# picrocope_hub_v3r1.net
KiCad netlist of a schematic drawn in EAGLE
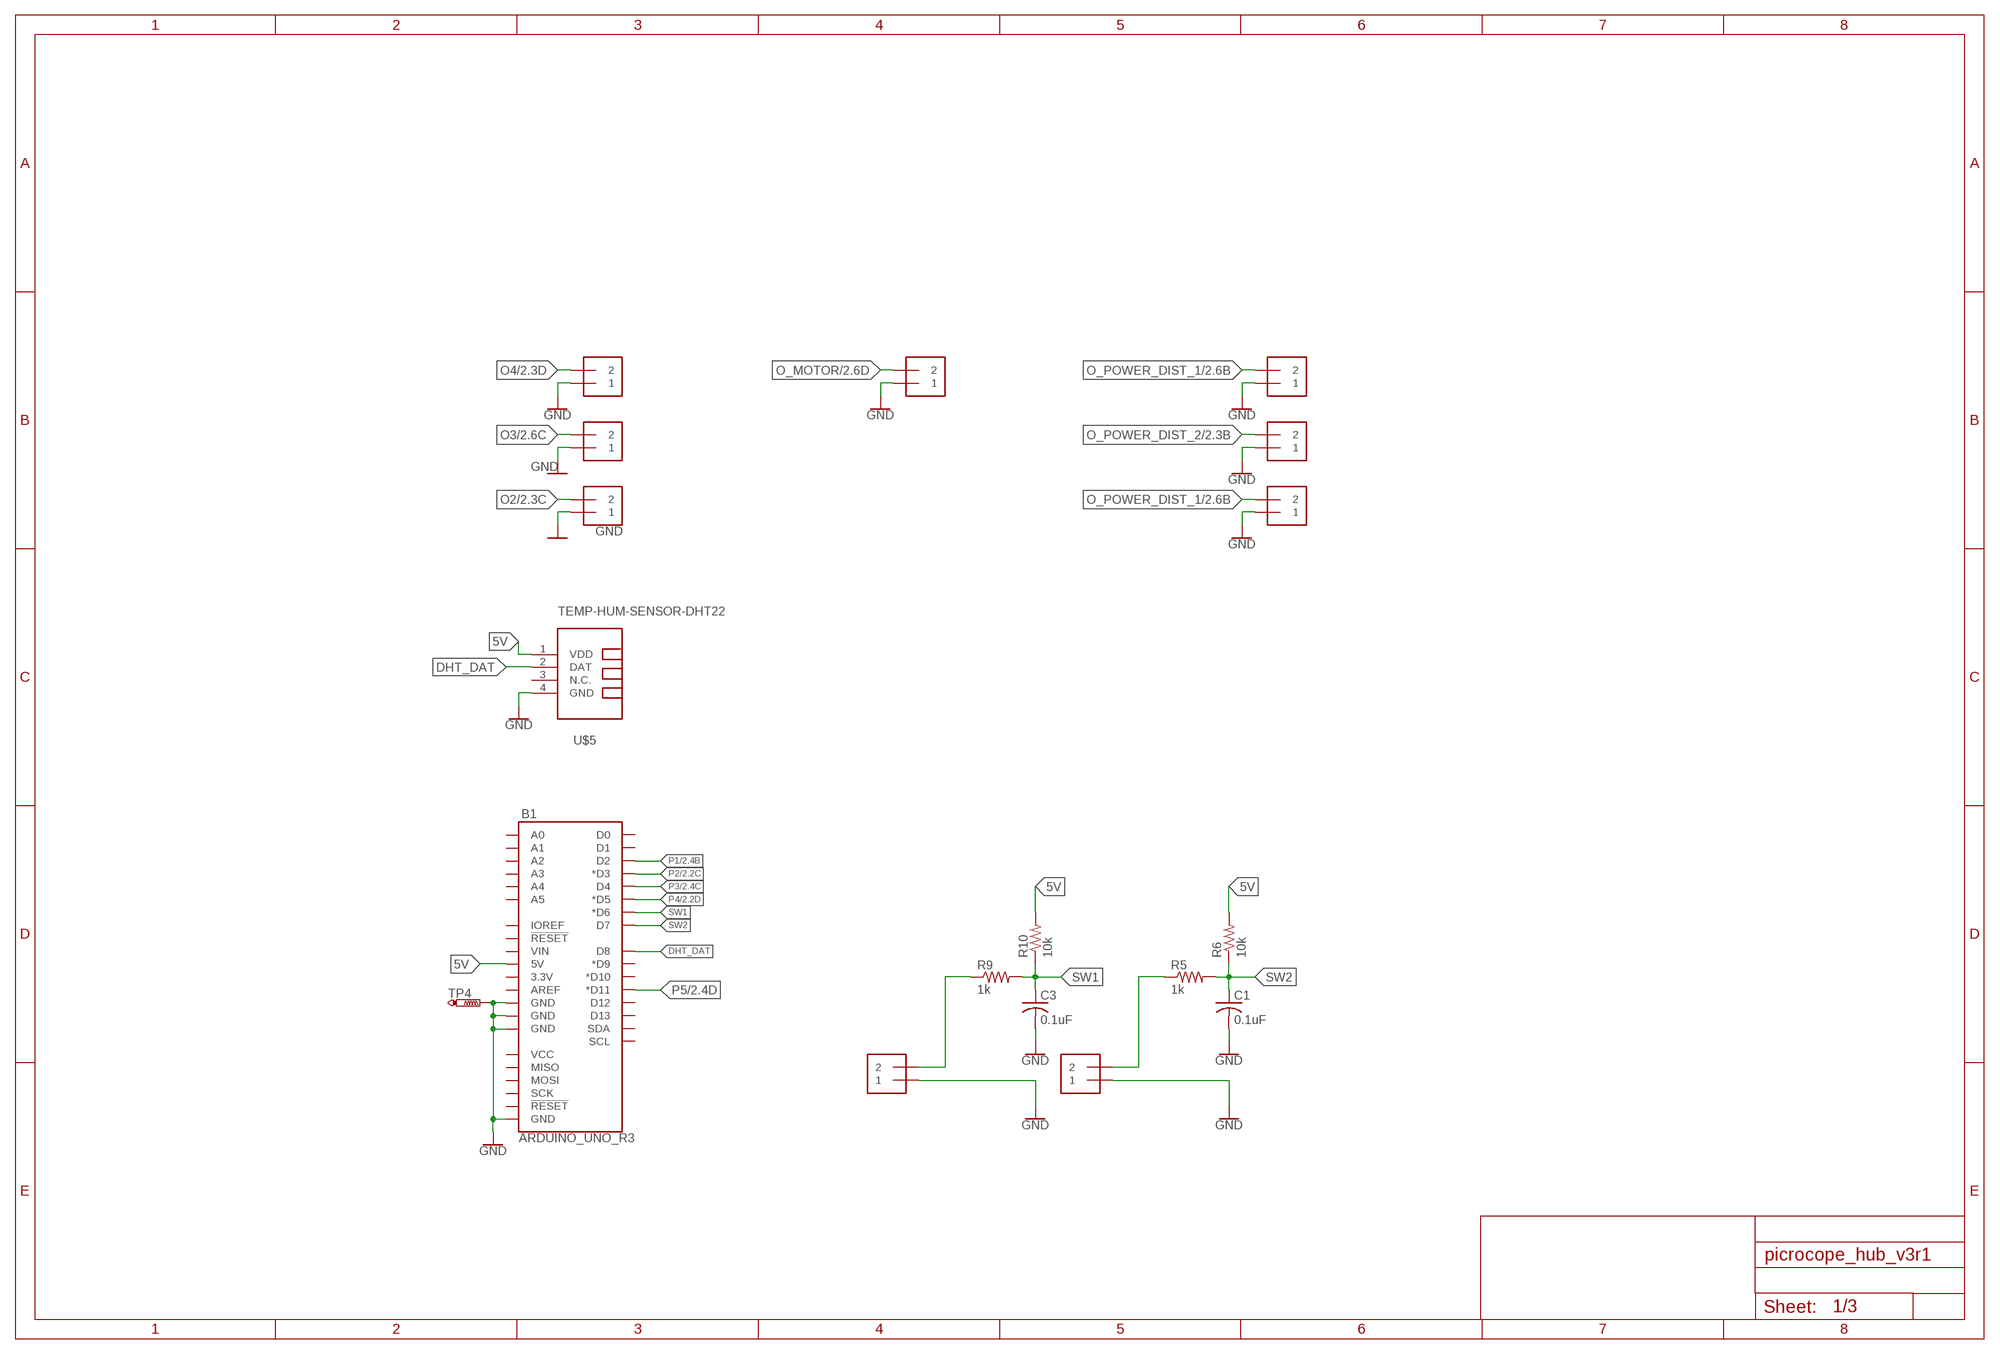
[diagram p0: schematic, sheet 1]
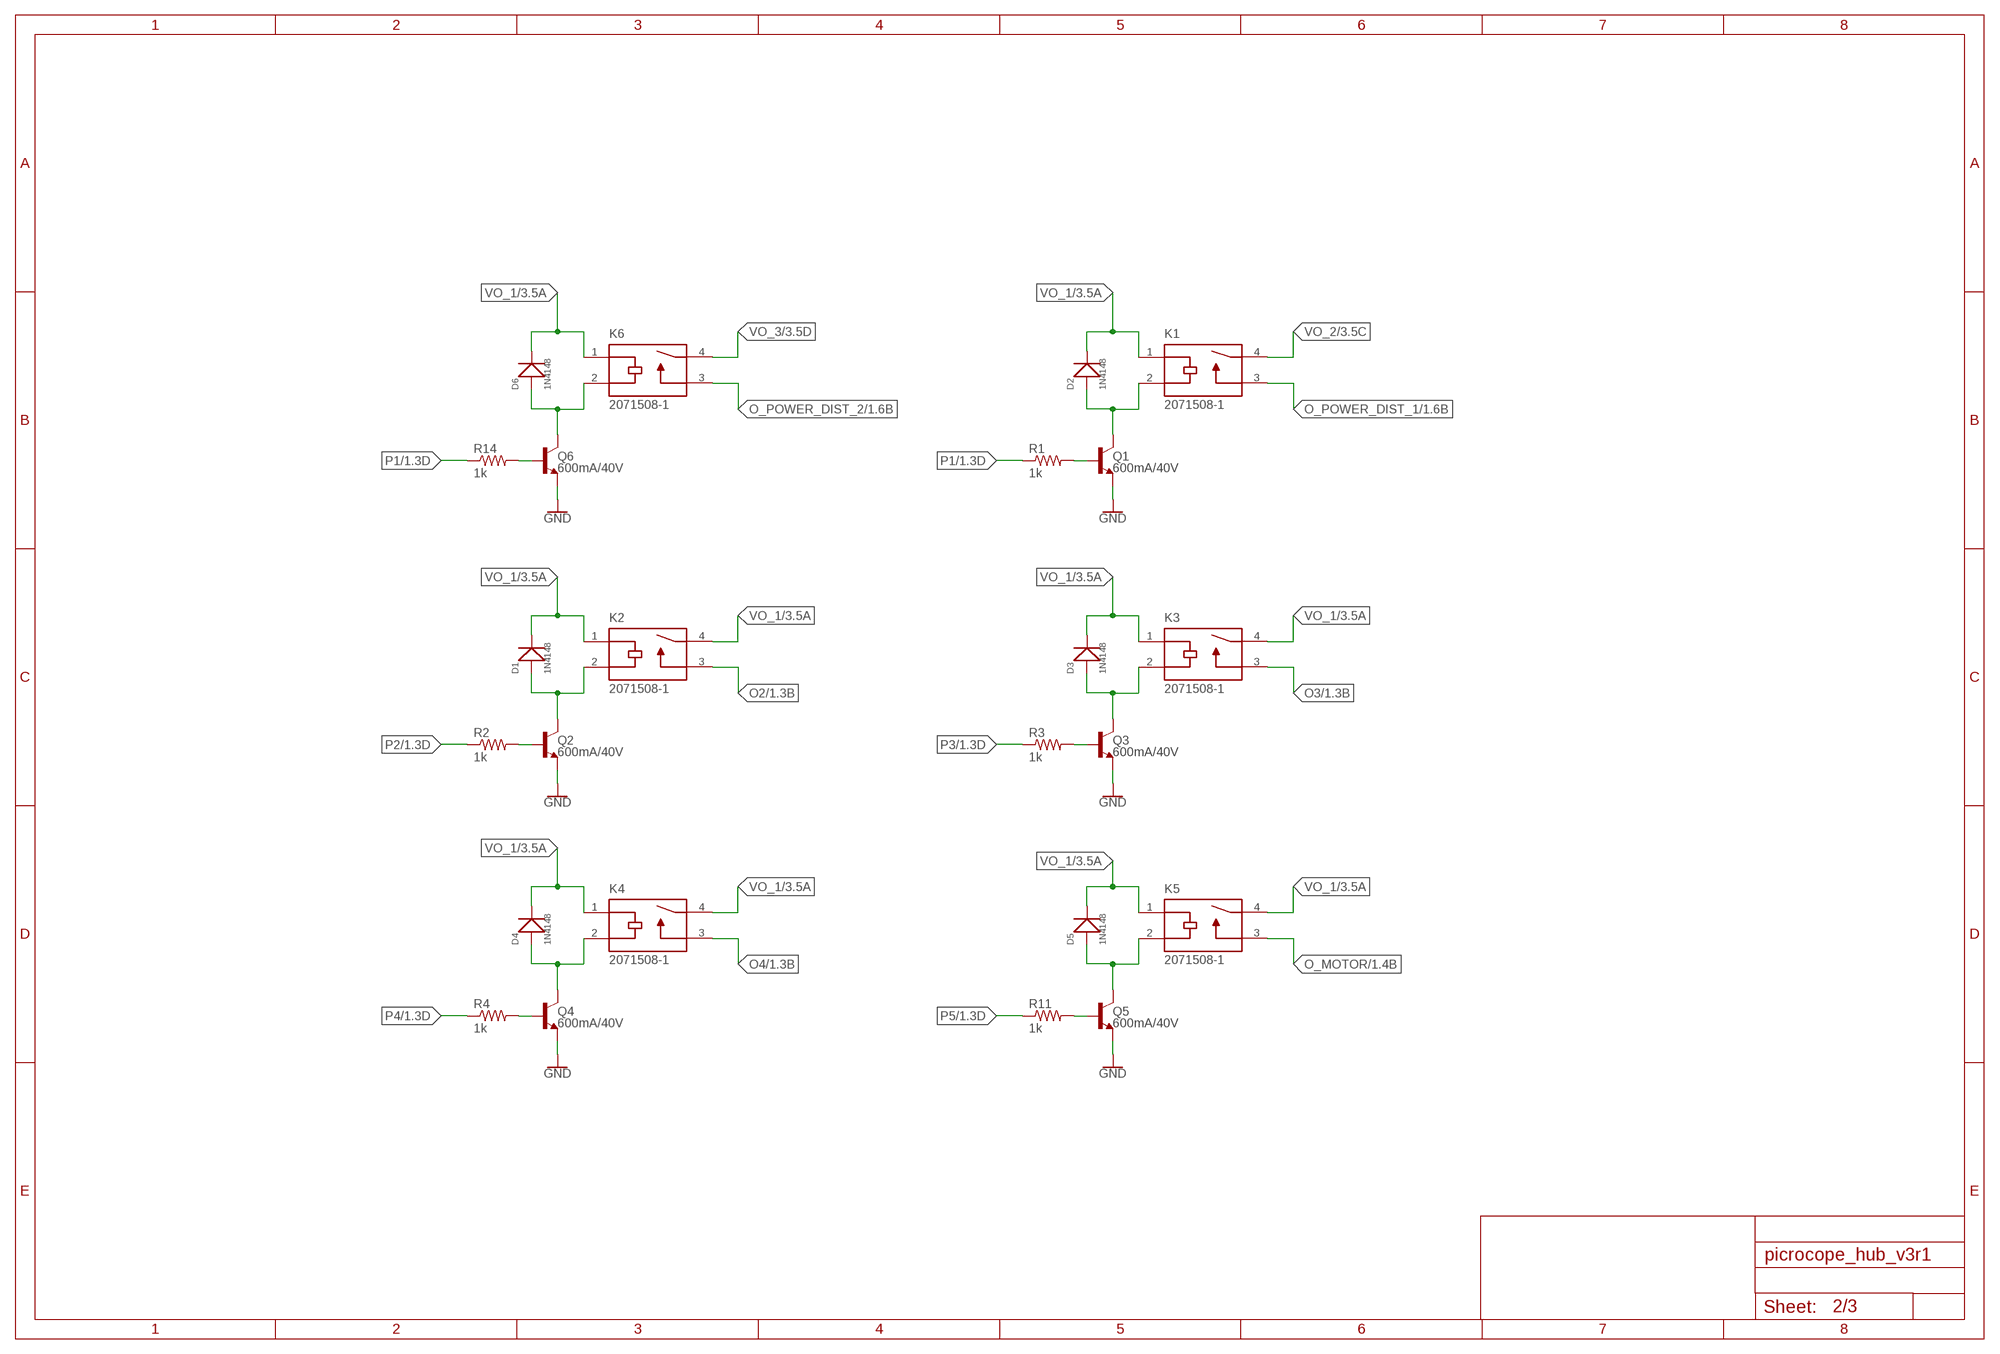
[diagram p1: schematic, sheet 2]
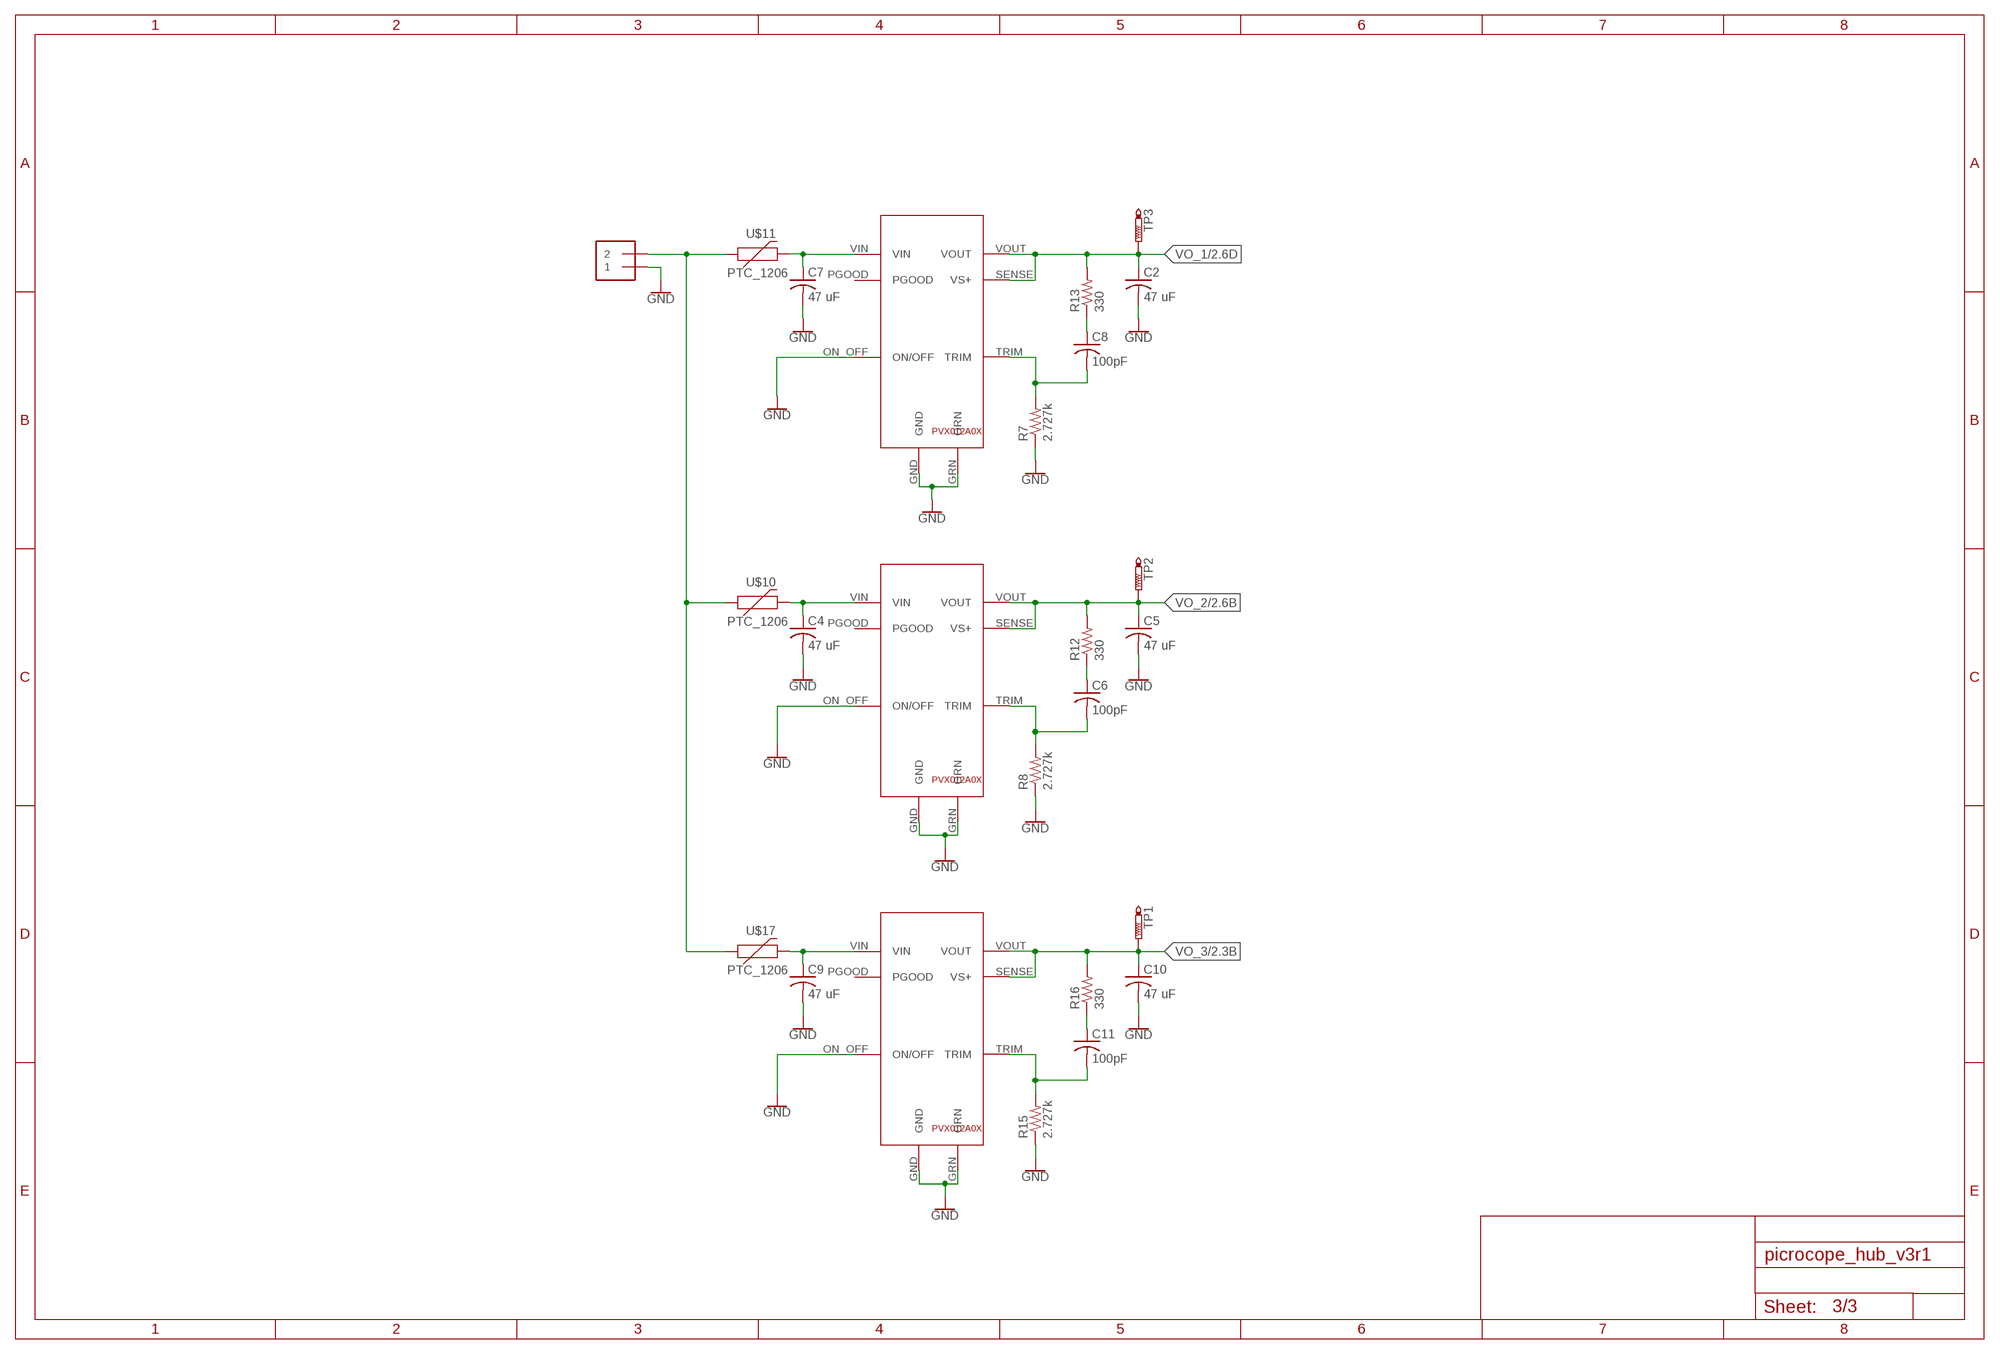
[diagram p2: schematic, sheet 3]

(export (version "E")
  (design (tool "Eeschema 10.0.6"))
  (components
    (comp (ref "C2")
      (value "47 uF")
      (footprint "eagle-import:C1210")
      (libsource (lib "eagle-import") (part "C-USC1210"))
    )
    (comp (ref "C4")
      (value "47 uF")
      (footprint "eagle-import:C1210")
      (libsource (lib "eagle-import") (part "C-USC1210"))
    )
    (comp (ref "C5")
      (value "47 uF")
      (footprint "eagle-import:C1210")
      (libsource (lib "eagle-import") (part "C-USC1210"))
    )
    (comp (ref "C6")
      (value "100pF")
      (footprint "eagle-import:C0603")
      (libsource (lib "eagle-import") (part "C-USC0603"))
    )
    (comp (ref "C7")
      (value "47 uF")
      (footprint "eagle-import:C1210")
      (libsource (lib "eagle-import") (part "C-USC1210"))
    )
    (comp (ref "C8")
      (value "100pF")
      (footprint "eagle-import:C0603")
      (libsource (lib "eagle-import") (part "C-USC0603"))
    )
    (comp (ref "C9")
      (value "47 uF")
      (footprint "eagle-import:C1210")
      (libsource (lib "eagle-import") (part "C-USC1210"))
    )
    (comp (ref "C10")
      (value "47 uF")
      (footprint "eagle-import:C1210")
      (libsource (lib "eagle-import") (part "C-USC1210"))
    )
    (comp (ref "C11")
      (value "100pF")
      (footprint "eagle-import:C0603")
      (libsource (lib "eagle-import") (part "C-USC0603"))
    )
    (comp (ref "R7")
      (value "2.727k")
      (footprint "eagle-import:R0603")
      (libsource (lib "eagle-import") (part "R-US_R0603"))
    )
    (comp (ref "R8")
      (value "2.727k")
      (footprint "eagle-import:R0603")
      (libsource (lib "eagle-import") (part "R-US_R0603"))
    )
    (comp (ref "R12")
      (value "330")
      (footprint "eagle-import:R0603")
      (libsource (lib "eagle-import") (part "R-US_R0603"))
    )
    (comp (ref "R13")
      (value "330")
      (footprint "eagle-import:R0603")
      (libsource (lib "eagle-import") (part "R-US_R0603"))
    )
    (comp (ref "R15")
      (value "2.727k")
      (footprint "eagle-import:R0603")
      (libsource (lib "eagle-import") (part "R-US_R0603"))
    )
    (comp (ref "R16")
      (value "330")
      (footprint "eagle-import:R0603")
      (libsource (lib "eagle-import") (part "R-US_R0603"))
    )
    (comp (ref "TP1")
      (value "PTR1B1,27")
      (footprint "eagle-import:B1,27")
      (libsource (lib "eagle-import") (part "PTR1B1,27"))
    )
    (comp (ref "TP2")
      (value "PTR1B1,27")
      (footprint "eagle-import:B1,27")
      (libsource (lib "eagle-import") (part "PTR1B1,27"))
    )
    (comp (ref "TP3")
      (value "PTR1B1,27")
      (footprint "eagle-import:B1,27")
      (libsource (lib "eagle-import") (part "PTR1B1,27"))
    )
    (comp (ref "U$1")
      (value "PVX012A0XV1")
      (footprint "eagle-import:PVX012A0X")
      (libsource (lib "eagle-import") (part "PVX012A0XV1"))
    )
    (comp (ref "U$2")
      (value "PVX012A0XV1")
      (footprint "eagle-import:PVX012A0X")
      (libsource (lib "eagle-import") (part "PVX012A0XV1"))
    )
    (comp (ref "U$3")
      (value "MOLEX_0039301022")
      (footprint "eagle-import:MINI-FIT_JR_CONN")
      (libsource (lib "eagle-import") (part "MOLEX_0039301022"))
    )
    (comp (ref "U$4")
      (value "PVX012A0XV1")
      (footprint "eagle-import:PVX012A0X")
      (libsource (lib "eagle-import") (part "PVX012A0XV1"))
    )
    (comp (ref "U$10")
      (value "PTC_1206")
      (footprint "eagle-import:1206")
      (libsource (lib "eagle-import") (part "PTC_1206"))
    )
    (comp (ref "U$11")
      (value "PTC_1206")
      (footprint "eagle-import:1206")
      (libsource (lib "eagle-import") (part "PTC_1206"))
    )
    (comp (ref "U$17")
      (value "PTC_1206")
      (footprint "eagle-import:1206")
      (libsource (lib "eagle-import") (part "PTC_1206"))
    )
    (comp (ref "B1")
      (value "ARDUINO_UNO_R3")
      (footprint "eagle-import:ARDUINO_R3")
      (libsource (lib "eagle-import") (part "ARDUINO_UNO_R3"))
    )
    (comp (ref "C1")
      (value "0.1uF")
      (footprint "eagle-import:C0603")
      (libsource (lib "eagle-import") (part "C-USC0603"))
    )
    (comp (ref "C3")
      (value "0.1uF")
      (footprint "eagle-import:C0603")
      (libsource (lib "eagle-import") (part "C-USC0603"))
    )
    (comp (ref "R5")
      (value "1k")
      (footprint "eagle-import:R0603")
      (libsource (lib "eagle-import") (part "resistor_348_R-US_R0603"))
    )
    (comp (ref "R6")
      (value "10k")
      (footprint "eagle-import:R0603")
      (libsource (lib "eagle-import") (part "resistor_348_R-US_R0603"))
    )
    (comp (ref "R9")
      (value "1k")
      (footprint "eagle-import:R0603")
      (libsource (lib "eagle-import") (part "resistor_348_R-US_R0603"))
    )
    (comp (ref "R10")
      (value "10k")
      (footprint "eagle-import:R0603")
      (libsource (lib "eagle-import") (part "resistor_348_R-US_R0603"))
    )
    (comp (ref "TP4")
      (value "PTR1B1,27")
      (footprint "eagle-import:B1,27")
      (libsource (lib "eagle-import") (part "PTR1B1,27"))
    )
    (comp (ref "U$5")
      (value "TEMP-HUM-SENSOR-DHT22")
      (footprint "eagle-import:TEMP-HUM-SENSOR-DHT22")
      (libsource (lib "eagle-import") (part "TEMP-HUM-SENSOR-DHT22"))
    )
    (comp (ref "U$6")
      (value "MOLEX_0039301022")
      (footprint "eagle-import:MINI-FIT_JR_CONN")
      (libsource (lib "eagle-import") (part "MOLEX_0039301022"))
    )
    (comp (ref "U$7")
      (value "MOLEX_0039301022")
      (footprint "eagle-import:MINI-FIT_JR_CONN")
      (libsource (lib "eagle-import") (part "MOLEX_0039301022"))
    )
    (comp (ref "U$8")
      (value "MOLEX_0039301022")
      (footprint "eagle-import:MINI-FIT_JR_CONN")
      (libsource (lib "eagle-import") (part "MOLEX_0039301022"))
    )
    (comp (ref "U$9")
      (value "MOLEX_0039301022")
      (footprint "eagle-import:MINI-FIT_JR_CONN")
      (libsource (lib "eagle-import") (part "MOLEX_0039301022"))
    )
    (comp (ref "U$12")
      (value "MOLEX_0039301022")
      (footprint "eagle-import:MINI-FIT_JR_CONN")
      (libsource (lib "eagle-import") (part "MOLEX_0039301022"))
    )
    (comp (ref "U$13")
      (value "MOLEX_0039301022")
      (footprint "eagle-import:MINI-FIT_JR_CONN")
      (libsource (lib "eagle-import") (part "MOLEX_0039301022"))
    )
    (comp (ref "U$14")
      (value "MOLEX_0039301022")
      (footprint "eagle-import:MINI-FIT_JR_CONN")
      (libsource (lib "eagle-import") (part "MOLEX_0039301022"))
    )
    (comp (ref "U$15")
      (value "MOLEX_0039301022")
      (footprint "eagle-import:MINI-FIT_JR_CONN")
      (libsource (lib "eagle-import") (part "MOLEX_0039301022"))
    )
    (comp (ref "U$18")
      (value "MOLEX_0039301022")
      (footprint "eagle-import:MINI-FIT_JR_CONN")
      (libsource (lib "eagle-import") (part "MOLEX_0039301022"))
    )
    (comp (ref "D1")
      (value "1N4148")
      (footprint "eagle-import:LL-34")
      (libsource (lib "eagle-import") (part "SMD-DIODE-SWITCH-1N4148(LL-34)"))
    )
    (comp (ref "D2")
      (value "1N4148")
      (footprint "eagle-import:LL-34")
      (libsource (lib "eagle-import") (part "SMD-DIODE-SWITCH-1N4148(LL-34)"))
    )
    (comp (ref "D3")
      (value "1N4148")
      (footprint "eagle-import:LL-34")
      (libsource (lib "eagle-import") (part "SMD-DIODE-SWITCH-1N4148(LL-34)"))
    )
    (comp (ref "D4")
      (value "1N4148")
      (footprint "eagle-import:LL-34")
      (libsource (lib "eagle-import") (part "SMD-DIODE-SWITCH-1N4148(LL-34)"))
    )
    (comp (ref "D5")
      (value "1N4148")
      (footprint "eagle-import:LL-34")
      (libsource (lib "eagle-import") (part "SMD-DIODE-SWITCH-1N4148(LL-34)"))
    )
    (comp (ref "D6")
      (value "1N4148")
      (footprint "eagle-import:LL-34")
      (libsource (lib "eagle-import") (part "SMD-DIODE-SWITCH-1N4148(LL-34)"))
    )
    (comp (ref "K1")
      (value "2071508-1")
      (footprint "eagle-import:RELAY_2071508-1")
      (fields (field (name "MANUFACTURER") "TE Connectivity"))
      (libsource (lib "eagle-import") (part "2071508-1"))
    )
    (comp (ref "K2")
      (value "2071508-1")
      (footprint "eagle-import:RELAY_2071508-1")
      (fields (field (name "MANUFACTURER") "TE Connectivity"))
      (libsource (lib "eagle-import") (part "2071508-1"))
    )
    (comp (ref "K3")
      (value "2071508-1")
      (footprint "eagle-import:RELAY_2071508-1")
      (fields (field (name "MANUFACTURER") "TE Connectivity"))
      (libsource (lib "eagle-import") (part "2071508-1"))
    )
    (comp (ref "K4")
      (value "2071508-1")
      (footprint "eagle-import:RELAY_2071508-1")
      (fields (field (name "MANUFACTURER") "TE Connectivity"))
      (libsource (lib "eagle-import") (part "2071508-1"))
    )
    (comp (ref "K5")
      (value "2071508-1")
      (footprint "eagle-import:RELAY_2071508-1")
      (fields (field (name "MANUFACTURER") "TE Connectivity"))
      (libsource (lib "eagle-import") (part "2071508-1"))
    )
    (comp (ref "K6")
      (value "2071508-1")
      (footprint "eagle-import:RELAY_2071508-1")
      (fields (field (name "MANUFACTURER") "TE Connectivity"))
      (libsource (lib "eagle-import") (part "2071508-1"))
    )
    (comp (ref "Q1")
      (value "600mA/40V")
      (footprint "eagle-import:SOT23-3")
      (libsource (lib "eagle-import") (part "TRANS_NPN-MMBT2222AL"))
    )
    (comp (ref "Q2")
      (value "600mA/40V")
      (footprint "eagle-import:SOT23-3")
      (libsource (lib "eagle-import") (part "TRANS_NPN-MMBT2222AL"))
    )
    (comp (ref "Q3")
      (value "600mA/40V")
      (footprint "eagle-import:SOT23-3")
      (libsource (lib "eagle-import") (part "TRANS_NPN-MMBT2222AL"))
    )
    (comp (ref "Q4")
      (value "600mA/40V")
      (footprint "eagle-import:SOT23-3")
      (libsource (lib "eagle-import") (part "TRANS_NPN-MMBT2222AL"))
    )
    (comp (ref "Q5")
      (value "600mA/40V")
      (footprint "eagle-import:SOT23-3")
      (libsource (lib "eagle-import") (part "TRANS_NPN-MMBT2222AL"))
    )
    (comp (ref "Q6")
      (value "600mA/40V")
      (footprint "eagle-import:SOT23-3")
      (libsource (lib "eagle-import") (part "TRANS_NPN-MMBT2222AL"))
    )
    (comp (ref "R1")
      (value "1k")
      (footprint "eagle-import:R0603")
      (libsource (lib "eagle-import") (part "resistor_348_R-US_R0603"))
    )
    (comp (ref "R2")
      (value "1k")
      (footprint "eagle-import:R0603")
      (libsource (lib "eagle-import") (part "resistor_348_R-US_R0603"))
    )
    (comp (ref "R3")
      (value "1k")
      (footprint "eagle-import:R0603")
      (libsource (lib "eagle-import") (part "resistor_348_R-US_R0603"))
    )
    (comp (ref "R4")
      (value "1k")
      (footprint "eagle-import:R0603")
      (libsource (lib "eagle-import") (part "resistor_348_R-US_R0603"))
    )
    (comp (ref "R11")
      (value "1k")
      (footprint "eagle-import:R0603")
      (libsource (lib "eagle-import") (part "resistor_348_R-US_R0603"))
    )
    (comp (ref "R14")
      (value "1k")
      (footprint "eagle-import:R0603")
      (libsource (lib "eagle-import") (part "resistor_348_R-US_R0603"))
    )
  )
  (nets
    (net (code "1") (name "5V") (class "Default")
      (node (ref "B1") (pin "5V") (pinfunction "5V_5V") (pintype "bidirectional"))
      (node (ref "R10") (pin "2") (pinfunction "2_2") (pintype "passive"))
      (node (ref "R6") (pin "2") (pinfunction "2_2") (pintype "passive"))
      (node (ref "U$5") (pin "1") (pinfunction "VDD_1") (pintype "power_in"))
    )
    (net (code "2") (name "DHT_DAT") (class "Default")
      (node (ref "B1") (pin "D8") (pinfunction "D8_D8") (pintype "bidirectional"))
      (node (ref "U$5") (pin "2") (pinfunction "DAT_2") (pintype "bidirectional"))
    )
    (net (code "3") (name "GND") (class "Default")
      (node (ref "B1") (pin "GND@1") (pinfunction "GND_GND@1") (pintype "bidirectional"))
      (node (ref "B1") (pin "GND@2") (pinfunction "GND_GND@2") (pintype "bidirectional"))
      (node (ref "B1") (pin "GND@3") (pinfunction "GND_GND@3") (pintype "bidirectional"))
      (node (ref "B1") (pin "GND@4") (pinfunction "GND_GND@4") (pintype "bidirectional"))
      (node (ref "C1") (pin "2") (pinfunction "2_2") (pintype "passive"))
      (node (ref "C10") (pin "2") (pinfunction "2_2") (pintype "passive"))
      (node (ref "C2") (pin "2") (pinfunction "2_2") (pintype "passive"))
      (node (ref "C3") (pin "2") (pinfunction "2_2") (pintype "passive"))
      (node (ref "C4") (pin "2") (pinfunction "2_2") (pintype "passive"))
      (node (ref "C5") (pin "2") (pinfunction "2_2") (pintype "passive"))
      (node (ref "C7") (pin "2") (pinfunction "2_2") (pintype "passive"))
      (node (ref "C9") (pin "2") (pinfunction "2_2") (pintype "passive"))
      (node (ref "Q1") (pin "2") (pinfunction "E_2") (pintype "passive"))
      (node (ref "Q2") (pin "2") (pinfunction "E_2") (pintype "passive"))
      (node (ref "Q3") (pin "2") (pinfunction "E_2") (pintype "passive"))
      (node (ref "Q4") (pin "2") (pinfunction "E_2") (pintype "passive"))
      (node (ref "Q5") (pin "2") (pinfunction "E_2") (pintype "passive"))
      (node (ref "Q6") (pin "2") (pinfunction "E_2") (pintype "passive"))
      (node (ref "R15") (pin "1") (pinfunction "1_1") (pintype "passive"))
      (node (ref "R7") (pin "1") (pinfunction "1_1") (pintype "passive"))
      (node (ref "R8") (pin "1") (pinfunction "1_1") (pintype "passive"))
      (node (ref "TP4") (pin "TP") (pinfunction "TP_TP") (pintype "input"))
      (node (ref "U$1") (pin "GND") (pinfunction "GND_GND") (pintype "bidirectional"))
      (node (ref "U$1") (pin "GRN") (pinfunction "GRN_GRN") (pintype "bidirectional"))
      (node (ref "U$1") (pin "ON_OFF") (pinfunction "ON/OFF_ON_OFF") (pintype "bidirectional"))
      (node (ref "U$12") (pin "P$2") (pinfunction "1_P$2") (pintype "passive"))
      (node (ref "U$13") (pin "P$2") (pinfunction "1_P$2") (pintype "passive"))
      (node (ref "U$14") (pin "P$2") (pinfunction "1_P$2") (pintype "passive"))
      (node (ref "U$15") (pin "P$2") (pinfunction "1_P$2") (pintype "passive"))
      (node (ref "U$18") (pin "P$2") (pinfunction "1_P$2") (pintype "passive"))
      (node (ref "U$2") (pin "GND") (pinfunction "GND_GND") (pintype "bidirectional"))
      (node (ref "U$2") (pin "GRN") (pinfunction "GRN_GRN") (pintype "bidirectional"))
      (node (ref "U$2") (pin "ON_OFF") (pinfunction "ON/OFF_ON_OFF") (pintype "bidirectional"))
      (node (ref "U$3") (pin "P$2") (pinfunction "1_P$2") (pintype "passive"))
      (node (ref "U$4") (pin "GND") (pinfunction "GND_GND") (pintype "bidirectional"))
      (node (ref "U$4") (pin "GRN") (pinfunction "GRN_GRN") (pintype "bidirectional"))
      (node (ref "U$4") (pin "ON_OFF") (pinfunction "ON/OFF_ON_OFF") (pintype "bidirectional"))
      (node (ref "U$5") (pin "4") (pinfunction "GND_4") (pintype "power_in"))
      (node (ref "U$6") (pin "P$2") (pinfunction "1_P$2") (pintype "passive"))
      (node (ref "U$7") (pin "P$2") (pinfunction "1_P$2") (pintype "passive"))
      (node (ref "U$8") (pin "P$2") (pinfunction "1_P$2") (pintype "passive"))
      (node (ref "U$9") (pin "P$2") (pinfunction "1_P$2") (pintype "passive"))
    )
    (net (code "4") (name "Net-(C4-Pad1)") (class "Default")
      (node (ref "C4") (pin "1") (pinfunction "1_1") (pintype "passive"))
      (node (ref "U$10") (pin "2") (pinfunction "2_2") (pintype "bidirectional"))
      (node (ref "U$2") (pin "VIN") (pinfunction "VIN_VIN") (pintype "bidirectional"))
    )
    (net (code "5") (name "Net-(C6-Pad1)") (class "Default")
      (node (ref "C6") (pin "1") (pinfunction "1_1") (pintype "passive"))
      (node (ref "R12") (pin "1") (pinfunction "1_1") (pintype "passive"))
    )
    (net (code "6") (name "Net-(C6-Pad2)") (class "Default")
      (node (ref "C6") (pin "2") (pinfunction "2_2") (pintype "passive"))
      (node (ref "R8") (pin "2") (pinfunction "2_2") (pintype "passive"))
      (node (ref "U$2") (pin "TRIM") (pinfunction "TRIM_TRIM") (pintype "bidirectional"))
    )
    (net (code "7") (name "Net-(C7-Pad1)") (class "Default")
      (node (ref "C7") (pin "1") (pinfunction "1_1") (pintype "passive"))
      (node (ref "U$1") (pin "VIN") (pinfunction "VIN_VIN") (pintype "bidirectional"))
      (node (ref "U$11") (pin "2") (pinfunction "2_2") (pintype "bidirectional"))
    )
    (net (code "8") (name "Net-(C8-Pad1)") (class "Default")
      (node (ref "C8") (pin "1") (pinfunction "1_1") (pintype "passive"))
      (node (ref "R13") (pin "1") (pinfunction "1_1") (pintype "passive"))
    )
    (net (code "9") (name "Net-(C8-Pad2)") (class "Default")
      (node (ref "C8") (pin "2") (pinfunction "2_2") (pintype "passive"))
      (node (ref "R7") (pin "2") (pinfunction "2_2") (pintype "passive"))
      (node (ref "U$1") (pin "TRIM") (pinfunction "TRIM_TRIM") (pintype "bidirectional"))
    )
    (net (code "10") (name "Net-(C9-Pad1)") (class "Default")
      (node (ref "C9") (pin "1") (pinfunction "1_1") (pintype "passive"))
      (node (ref "U$17") (pin "2") (pinfunction "2_2") (pintype "bidirectional"))
      (node (ref "U$4") (pin "VIN") (pinfunction "VIN_VIN") (pintype "bidirectional"))
    )
    (net (code "11") (name "Net-(C11-Pad1)") (class "Default")
      (node (ref "C11") (pin "1") (pinfunction "1_1") (pintype "passive"))
      (node (ref "R16") (pin "1") (pinfunction "1_1") (pintype "passive"))
    )
    (net (code "12") (name "Net-(C11-Pad2)") (class "Default")
      (node (ref "C11") (pin "2") (pinfunction "2_2") (pintype "passive"))
      (node (ref "R15") (pin "2") (pinfunction "2_2") (pintype "passive"))
      (node (ref "U$4") (pin "TRIM") (pinfunction "TRIM_TRIM") (pintype "bidirectional"))
    )
    (net (code "13") (name "Net-(D1-+)") (class "Default")
      (node (ref "D1") (pin "A") (pinfunction "+_A") (pintype "passive"))
      (node (ref "K2") (pin "2") (pinfunction "COIL2_2") (pintype "passive"))
      (node (ref "Q2") (pin "3") (pinfunction "C_3") (pintype "passive"))
    )
    (net (code "14") (name "Net-(D2-+)") (class "Default")
      (node (ref "D2") (pin "A") (pinfunction "+_A") (pintype "passive"))
      (node (ref "K1") (pin "2") (pinfunction "COIL2_2") (pintype "passive"))
      (node (ref "Q1") (pin "3") (pinfunction "C_3") (pintype "passive"))
    )
    (net (code "15") (name "Net-(D3-+)") (class "Default")
      (node (ref "D3") (pin "A") (pinfunction "+_A") (pintype "passive"))
      (node (ref "K3") (pin "2") (pinfunction "COIL2_2") (pintype "passive"))
      (node (ref "Q3") (pin "3") (pinfunction "C_3") (pintype "passive"))
    )
    (net (code "16") (name "Net-(D4-+)") (class "Default")
      (node (ref "D4") (pin "A") (pinfunction "+_A") (pintype "passive"))
      (node (ref "K4") (pin "2") (pinfunction "COIL2_2") (pintype "passive"))
      (node (ref "Q4") (pin "3") (pinfunction "C_3") (pintype "passive"))
    )
    (net (code "17") (name "Net-(D5-+)") (class "Default")
      (node (ref "D5") (pin "A") (pinfunction "+_A") (pintype "passive"))
      (node (ref "K5") (pin "2") (pinfunction "COIL2_2") (pintype "passive"))
      (node (ref "Q5") (pin "3") (pinfunction "C_3") (pintype "passive"))
    )
    (net (code "18") (name "Net-(D6-+)") (class "Default")
      (node (ref "D6") (pin "A") (pinfunction "+_A") (pintype "passive"))
      (node (ref "K6") (pin "2") (pinfunction "COIL2_2") (pintype "passive"))
      (node (ref "Q6") (pin "3") (pinfunction "C_3") (pintype "passive"))
    )
    (net (code "19") (name "Net-(Q1-B)") (class "Default")
      (node (ref "Q1") (pin "1") (pinfunction "B_1") (pintype "passive"))
      (node (ref "R1") (pin "2") (pinfunction "2_2") (pintype "passive"))
    )
    (net (code "20") (name "Net-(Q2-B)") (class "Default")
      (node (ref "Q2") (pin "1") (pinfunction "B_1") (pintype "passive"))
      (node (ref "R2") (pin "2") (pinfunction "2_2") (pintype "passive"))
    )
    (net (code "21") (name "Net-(Q3-B)") (class "Default")
      (node (ref "Q3") (pin "1") (pinfunction "B_1") (pintype "passive"))
      (node (ref "R3") (pin "2") (pinfunction "2_2") (pintype "passive"))
    )
    (net (code "22") (name "Net-(Q4-B)") (class "Default")
      (node (ref "Q4") (pin "1") (pinfunction "B_1") (pintype "passive"))
      (node (ref "R4") (pin "2") (pinfunction "2_2") (pintype "passive"))
    )
    (net (code "23") (name "Net-(Q5-B)") (class "Default")
      (node (ref "Q5") (pin "1") (pinfunction "B_1") (pintype "passive"))
      (node (ref "R11") (pin "2") (pinfunction "2_2") (pintype "passive"))
    )
    (net (code "24") (name "Net-(Q6-B)") (class "Default")
      (node (ref "Q6") (pin "1") (pinfunction "B_1") (pintype "passive"))
      (node (ref "R14") (pin "2") (pinfunction "2_2") (pintype "passive"))
    )
    (net (code "25") (name "Net-(U$3-2)") (class "Default")
      (node (ref "U$10") (pin "1") (pinfunction "1_1") (pintype "bidirectional"))
      (node (ref "U$11") (pin "1") (pinfunction "1_1") (pintype "bidirectional"))
      (node (ref "U$17") (pin "1") (pinfunction "1_1") (pintype "bidirectional"))
      (node (ref "U$3") (pin "P$1") (pinfunction "2_P$1") (pintype "passive"))
    )
    (net (code "26") (name "Net-(U$15-2)") (class "Default")
      (node (ref "R9") (pin "1") (pinfunction "1_1") (pintype "passive"))
      (node (ref "U$15") (pin "P$1") (pinfunction "2_P$1") (pintype "passive"))
    )
    (net (code "27") (name "Net-(U$18-2)") (class "Default")
      (node (ref "R5") (pin "1") (pinfunction "1_1") (pintype "passive"))
      (node (ref "U$18") (pin "P$1") (pinfunction "2_P$1") (pintype "passive"))
    )
    (net (code "28") (name "O2") (class "Default")
      (node (ref "K2") (pin "3") (pinfunction "NO_3") (pintype "passive"))
      (node (ref "U$7") (pin "P$1") (pinfunction "2_P$1") (pintype "passive"))
    )
    (net (code "29") (name "O3") (class "Default")
      (node (ref "K3") (pin "3") (pinfunction "NO_3") (pintype "passive"))
      (node (ref "U$8") (pin "P$1") (pinfunction "2_P$1") (pintype "passive"))
    )
    (net (code "30") (name "O4") (class "Default")
      (node (ref "K4") (pin "3") (pinfunction "NO_3") (pintype "passive"))
      (node (ref "U$9") (pin "P$1") (pinfunction "2_P$1") (pintype "passive"))
    )
    (net (code "31") (name "O_MOTOR") (class "Default")
      (node (ref "K5") (pin "3") (pinfunction "NO_3") (pintype "passive"))
      (node (ref "U$14") (pin "P$1") (pinfunction "2_P$1") (pintype "passive"))
    )
    (net (code "32") (name "O_POWER_DIST_1") (class "Default")
      (node (ref "K1") (pin "3") (pinfunction "NO_3") (pintype "passive"))
      (node (ref "U$13") (pin "P$1") (pinfunction "2_P$1") (pintype "passive"))
      (node (ref "U$6") (pin "P$1") (pinfunction "2_P$1") (pintype "passive"))
    )
    (net (code "33") (name "O_POWER_DIST_2") (class "Default")
      (node (ref "K6") (pin "3") (pinfunction "NO_3") (pintype "passive"))
      (node (ref "U$12") (pin "P$1") (pinfunction "2_P$1") (pintype "passive"))
    )
    (net (code "34") (name "P1") (class "Default")
      (node (ref "B1") (pin "D2") (pinfunction "D2_D2") (pintype "bidirectional"))
      (node (ref "R1") (pin "1") (pinfunction "1_1") (pintype "passive"))
      (node (ref "R14") (pin "1") (pinfunction "1_1") (pintype "passive"))
    )
    (net (code "35") (name "P2") (class "Default")
      (node (ref "B1") (pin "D3") (pinfunction "*D3_D3") (pintype "bidirectional"))
      (node (ref "R2") (pin "1") (pinfunction "1_1") (pintype "passive"))
    )
    (net (code "36") (name "P3") (class "Default")
      (node (ref "B1") (pin "D4") (pinfunction "D4_D4") (pintype "bidirectional"))
      (node (ref "R3") (pin "1") (pinfunction "1_1") (pintype "passive"))
    )
    (net (code "37") (name "P4") (class "Default")
      (node (ref "B1") (pin "D5") (pinfunction "*D5_D5") (pintype "bidirectional"))
      (node (ref "R4") (pin "1") (pinfunction "1_1") (pintype "passive"))
    )
    (net (code "38") (name "P5") (class "Default")
      (node (ref "B1") (pin "D11") (pinfunction "*D11_D11") (pintype "bidirectional"))
      (node (ref "R11") (pin "1") (pinfunction "1_1") (pintype "passive"))
    )
    (net (code "39") (name "SW1") (class "Default")
      (node (ref "B1") (pin "D6") (pinfunction "*D6_D6") (pintype "bidirectional"))
      (node (ref "C3") (pin "1") (pinfunction "1_1") (pintype "passive"))
      (node (ref "R10") (pin "1") (pinfunction "1_1") (pintype "passive"))
      (node (ref "R9") (pin "2") (pinfunction "2_2") (pintype "passive"))
    )
    (net (code "40") (name "SW2") (class "Default")
      (node (ref "B1") (pin "D7") (pinfunction "D7_D7") (pintype "bidirectional"))
      (node (ref "C1") (pin "1") (pinfunction "1_1") (pintype "passive"))
      (node (ref "R5") (pin "2") (pinfunction "2_2") (pintype "passive"))
      (node (ref "R6") (pin "1") (pinfunction "1_1") (pintype "passive"))
    )
    (net (code "41") (name "VO_1") (class "Default")
      (node (ref "C2") (pin "1") (pinfunction "1_1") (pintype "passive"))
      (node (ref "D1") (pin "C") (pinfunction "-_C") (pintype "passive"))
      (node (ref "D2") (pin "C") (pinfunction "-_C") (pintype "passive"))
      (node (ref "D3") (pin "C") (pinfunction "-_C") (pintype "passive"))
      (node (ref "D4") (pin "C") (pinfunction "-_C") (pintype "passive"))
      (node (ref "D5") (pin "C") (pinfunction "-_C") (pintype "passive"))
      (node (ref "D6") (pin "C") (pinfunction "-_C") (pintype "passive"))
      (node (ref "K1") (pin "1") (pinfunction "COIL1_1") (pintype "passive"))
      (node (ref "K2") (pin "1") (pinfunction "COIL1_1") (pintype "passive"))
      (node (ref "K2") (pin "4") (pinfunction "COM_4") (pintype "passive"))
      (node (ref "K3") (pin "1") (pinfunction "COIL1_1") (pintype "passive"))
      (node (ref "K3") (pin "4") (pinfunction "COM_4") (pintype "passive"))
      (node (ref "K4") (pin "1") (pinfunction "COIL1_1") (pintype "passive"))
      (node (ref "K4") (pin "4") (pinfunction "COM_4") (pintype "passive"))
      (node (ref "K5") (pin "1") (pinfunction "COIL1_1") (pintype "passive"))
      (node (ref "K5") (pin "4") (pinfunction "COM_4") (pintype "passive"))
      (node (ref "K6") (pin "1") (pinfunction "COIL1_1") (pintype "passive"))
      (node (ref "R13") (pin "2") (pinfunction "2_2") (pintype "passive"))
      (node (ref "TP3") (pin "TP") (pinfunction "TP_TP") (pintype "input"))
      (node (ref "U$1") (pin "SENSE") (pinfunction "VS+_SENSE") (pintype "bidirectional"))
      (node (ref "U$1") (pin "VOUT") (pinfunction "VOUT_VOUT") (pintype "bidirectional"))
    )
    (net (code "42") (name "VO_2") (class "Default")
      (node (ref "C5") (pin "1") (pinfunction "1_1") (pintype "passive"))
      (node (ref "K1") (pin "4") (pinfunction "COM_4") (pintype "passive"))
      (node (ref "R12") (pin "2") (pinfunction "2_2") (pintype "passive"))
      (node (ref "TP2") (pin "TP") (pinfunction "TP_TP") (pintype "input"))
      (node (ref "U$2") (pin "SENSE") (pinfunction "VS+_SENSE") (pintype "bidirectional"))
      (node (ref "U$2") (pin "VOUT") (pinfunction "VOUT_VOUT") (pintype "bidirectional"))
    )
    (net (code "43") (name "VO_3") (class "Default")
      (node (ref "C10") (pin "1") (pinfunction "1_1") (pintype "passive"))
      (node (ref "K6") (pin "4") (pinfunction "COM_4") (pintype "passive"))
      (node (ref "R16") (pin "2") (pinfunction "2_2") (pintype "passive"))
      (node (ref "TP1") (pin "TP") (pinfunction "TP_TP") (pintype "input"))
      (node (ref "U$4") (pin "SENSE") (pinfunction "VS+_SENSE") (pintype "bidirectional"))
      (node (ref "U$4") (pin "VOUT") (pinfunction "VOUT_VOUT") (pintype "bidirectional"))
    )
    (net (code "44") (name "unconnected-(B1-*D9-PadD9)") (class "Default")
      (node (ref "B1") (pin "D9") (pinfunction "*D9_D9") (pintype "bidirectional"))
    )
    (net (code "45") (name "unconnected-(B1-*D10-PadD10)") (class "Default")
      (node (ref "B1") (pin "D10") (pinfunction "*D10_D10") (pintype "bidirectional"))
    )
    (net (code "46") (name "unconnected-(B1-Pad3.3V)") (class "Default")
      (node (ref "B1") (pin "3.3V") (pinfunction "3.3V_3.3V") (pintype "bidirectional"))
    )
    (net (code "47") (name "unconnected-(B1-PadA0)") (class "Default")
      (node (ref "B1") (pin "A0") (pinfunction "A0_A0") (pintype "bidirectional"))
    )
    (net (code "48") (name "unconnected-(B1-PadA1)") (class "Default")
      (node (ref "B1") (pin "A1") (pinfunction "A1_A1") (pintype "bidirectional"))
    )
    (net (code "49") (name "unconnected-(B1-PadA2)") (class "Default")
      (node (ref "B1") (pin "A2") (pinfunction "A2_A2") (pintype "bidirectional"))
    )
    (net (code "50") (name "unconnected-(B1-PadA3)") (class "Default")
      (node (ref "B1") (pin "A3") (pinfunction "A3_A3") (pintype "bidirectional"))
    )
    (net (code "51") (name "unconnected-(B1-PadA4)") (class "Default")
      (node (ref "B1") (pin "A4") (pinfunction "A4_A4") (pintype "bidirectional"))
    )
    (net (code "52") (name "unconnected-(B1-PadA5)") (class "Default")
      (node (ref "B1") (pin "A5") (pinfunction "A5_A5") (pintype "bidirectional"))
    )
    (net (code "53") (name "unconnected-(B1-PadAREF)") (class "Default")
      (node (ref "B1") (pin "AREF") (pinfunction "AREF_AREF") (pintype "bidirectional"))
    )
    (net (code "54") (name "unconnected-(B1-PadD0)") (class "Default")
      (node (ref "B1") (pin "D0") (pinfunction "D0_D0") (pintype "bidirectional"))
    )
    (net (code "55") (name "unconnected-(B1-PadD1)") (class "Default")
      (node (ref "B1") (pin "D1") (pinfunction "D1_D1") (pintype "bidirectional"))
    )
    (net (code "56") (name "unconnected-(B1-PadD12)") (class "Default")
      (node (ref "B1") (pin "D12") (pinfunction "D12_D12") (pintype "bidirectional"))
    )
    (net (code "57") (name "unconnected-(B1-PadD13)") (class "Default")
      (node (ref "B1") (pin "D13") (pinfunction "D13_D13") (pintype "bidirectional"))
    )
    (net (code "58") (name "unconnected-(B1-PadIOREF)") (class "Default")
      (node (ref "B1") (pin "IOREF") (pinfunction "IOREF_IOREF") (pintype "bidirectional"))
    )
    (net (code "59") (name "unconnected-(B1-PadMISO)") (class "Default")
      (node (ref "B1") (pin "MISO") (pinfunction "MISO_MISO") (pintype "bidirectional"))
    )
    (net (code "60") (name "unconnected-(B1-PadMOSI)") (class "Default")
      (node (ref "B1") (pin "MOSI") (pinfunction "MOSI_MOSI") (pintype "bidirectional"))
    )
    (net (code "61") (name "unconnected-(B1-PadSCK)") (class "Default")
      (node (ref "B1") (pin "SCK") (pinfunction "SCK_SCK") (pintype "bidirectional"))
    )
    (net (code "62") (name "unconnected-(B1-PadSCL)") (class "Default")
      (node (ref "B1") (pin "SCL") (pinfunction "SCL_SCL") (pintype "bidirectional"))
    )
    (net (code "63") (name "unconnected-(B1-PadSDA)") (class "Default")
      (node (ref "B1") (pin "SDA") (pinfunction "SDA_SDA") (pintype "bidirectional"))
    )
    (net (code "64") (name "unconnected-(B1-PadVCC)") (class "Default")
      (node (ref "B1") (pin "VCC") (pinfunction "VCC_VCC") (pintype "bidirectional"))
    )
    (net (code "65") (name "unconnected-(B1-PadVIN)") (class "Default")
      (node (ref "B1") (pin "VIN") (pinfunction "VIN_VIN") (pintype "bidirectional"))
    )
    (net (code "66") (name "unconnected-(B1-~{RESET}-PadRESET@1)") (class "Default")
      (node (ref "B1") (pin "RESET@1") (pinfunction "~{RESET}_RESET@1") (pintype "bidirectional"))
    )
    (net (code "67") (name "unconnected-(B1-~{RESET}-PadRESET@2)") (class "Default")
      (node (ref "B1") (pin "RESET@2") (pinfunction "~{RESET}_RESET@2") (pintype "bidirectional"))
    )
    (net (code "68") (name "unconnected-(U$1-PadPGOOD)") (class "Default")
      (node (ref "U$1") (pin "PGOOD") (pinfunction "PGOOD_PGOOD") (pintype "bidirectional"))
    )
    (net (code "69") (name "unconnected-(U$2-PadPGOOD)") (class "Default")
      (node (ref "U$2") (pin "PGOOD") (pinfunction "PGOOD_PGOOD") (pintype "bidirectional"))
    )
    (net (code "70") (name "unconnected-(U$4-PadPGOOD)") (class "Default")
      (node (ref "U$4") (pin "PGOOD") (pinfunction "PGOOD_PGOOD") (pintype "bidirectional"))
    )
    (net (code "71") (name "unconnected-(U$5-N.C.-Pad3)") (class "Default")
      (node (ref "U$5") (pin "3") (pinfunction "N.C._3") (pintype "passive"))
    )
  )
)
